# Eth_Conn.net
KiCad netlist of a schematic drawn in Altium Designer
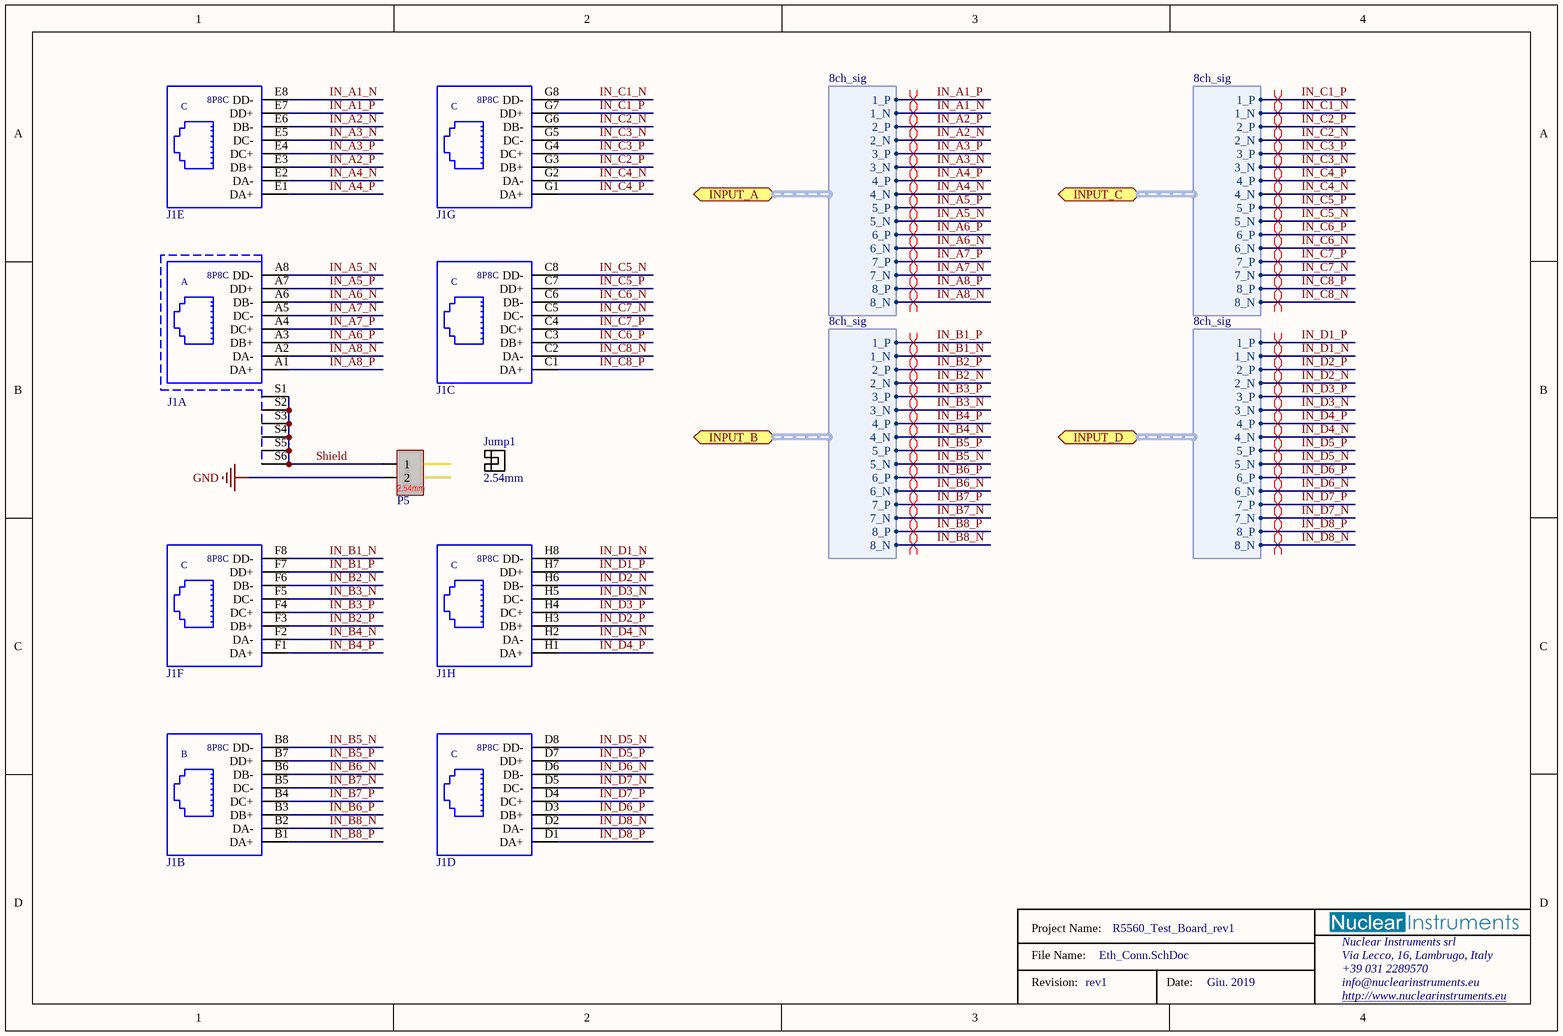
[diagram p0: Eth_Conn.SchDoc]

(export (version "E")
  (design (tool "Eeschema 10.0.6"))
  (components
    (comp (ref "J1")
      (value "Wurth_WR-MJ_RJ45_2x4_615064243321")
      (footprint "Wurth_WR-MJ_RJ45_2x4_615064243321")
      (description "RJ45 Modular Jack 2x4")
      (libsource (lib "Board_Wire_Connectors__SARAversion-84") (part "Wurth_WR-MJ_RJ45_2x4_615064243321"))
    )
    (comp (ref "Jump1") (value "2.54mm") (libsource (lib "Mechanical__SARAversion-78") (part "SNT-100-BK-G")))
    (comp (ref "P5")
      (value "Wurth_WR-PHD_2way_2.54mm_male")
      (footprint "Wurth_WR-PHD_2way_2.54mm_male")
      (description "Male 2 way 2.54 mm")
      (libsource (lib "Strip_Connectors__SARAversion-14") (part "Wurth_WR-PHD_2way_2.54mm_male"))
    )
  )
  (nets
    (net (code "2") (name "/IN_A1_N") (class "Default")
      (node (ref "J1") (pin "E8") (pinfunction "DD-_E8") (pintype "passive"))
    )
    (net (code "3") (name "/IN_A1_P") (class "Default")
      (node (ref "J1") (pin "E7") (pinfunction "DD+_E7") (pintype "passive"))
    )
    (net (code "4") (name "/IN_A2_N") (class "Default")
      (node (ref "J1") (pin "E6") (pinfunction "DB-_E6") (pintype "passive"))
    )
    (net (code "5") (name "/IN_A2_P") (class "Default")
      (node (ref "J1") (pin "E3") (pinfunction "DB+_E3") (pintype "passive"))
    )
    (net (code "6") (name "/IN_A3_N") (class "Default")
      (node (ref "J1") (pin "E5") (pinfunction "DC-_E5") (pintype "passive"))
    )
    (net (code "7") (name "/IN_A3_P") (class "Default")
      (node (ref "J1") (pin "E4") (pinfunction "DC+_E4") (pintype "passive"))
    )
    (net (code "8") (name "/IN_A4_N") (class "Default")
      (node (ref "J1") (pin "E2") (pinfunction "DA-_E2") (pintype "passive"))
    )
    (net (code "9") (name "/IN_A4_P") (class "Default")
      (node (ref "J1") (pin "E1") (pinfunction "DA+_E1") (pintype "passive"))
    )
    (net (code "10") (name "/IN_A5_N") (class "Default")
      (node (ref "J1") (pin "A8") (pinfunction "DD-_A8") (pintype "passive"))
    )
    (net (code "11") (name "/IN_A5_P") (class "Default")
      (node (ref "J1") (pin "A7") (pinfunction "DD+_A7") (pintype "passive"))
    )
    (net (code "12") (name "/IN_A6_N") (class "Default")
      (node (ref "J1") (pin "A6") (pinfunction "DB-_A6") (pintype "passive"))
    )
    (net (code "13") (name "/IN_A6_P") (class "Default")
      (node (ref "J1") (pin "A3") (pinfunction "DB+_A3") (pintype "passive"))
    )
    (net (code "14") (name "/IN_A7_N") (class "Default")
      (node (ref "J1") (pin "A5") (pinfunction "DC-_A5") (pintype "passive"))
    )
    (net (code "15") (name "/IN_A7_P") (class "Default")
      (node (ref "J1") (pin "A4") (pinfunction "DC+_A4") (pintype "passive"))
    )
    (net (code "16") (name "/IN_A8_N") (class "Default")
      (node (ref "J1") (pin "A2") (pinfunction "DA-_A2") (pintype "passive"))
    )
    (net (code "17") (name "/IN_A8_P") (class "Default")
      (node (ref "J1") (pin "A1") (pinfunction "DA+_A1") (pintype "passive"))
    )
    (net (code "18") (name "/IN_B1_N") (class "Default")
      (node (ref "J1") (pin "F8") (pinfunction "DD-_F8") (pintype "passive"))
    )
    (net (code "19") (name "/IN_B1_P") (class "Default")
      (node (ref "J1") (pin "F7") (pinfunction "DD+_F7") (pintype "passive"))
    )
    (net (code "20") (name "/IN_B2_N") (class "Default")
      (node (ref "J1") (pin "F6") (pinfunction "DB-_F6") (pintype "passive"))
    )
    (net (code "21") (name "/IN_B2_P") (class "Default")
      (node (ref "J1") (pin "F3") (pinfunction "DB+_F3") (pintype "passive"))
    )
    (net (code "22") (name "/IN_B3_N") (class "Default")
      (node (ref "J1") (pin "F5") (pinfunction "DC-_F5") (pintype "passive"))
    )
    (net (code "23") (name "/IN_B3_P") (class "Default")
      (node (ref "J1") (pin "F4") (pinfunction "DC+_F4") (pintype "passive"))
    )
    (net (code "24") (name "/IN_B4_N") (class "Default")
      (node (ref "J1") (pin "F2") (pinfunction "DA-_F2") (pintype "passive"))
    )
    (net (code "25") (name "/IN_B4_P") (class "Default")
      (node (ref "J1") (pin "F1") (pinfunction "DA+_F1") (pintype "passive"))
    )
    (net (code "26") (name "/IN_B5_N") (class "Default")
      (node (ref "J1") (pin "B8") (pinfunction "DD-_B8") (pintype "passive"))
    )
    (net (code "27") (name "/IN_B5_P") (class "Default")
      (node (ref "J1") (pin "B7") (pinfunction "DD+_B7") (pintype "passive"))
    )
    (net (code "28") (name "/IN_B6_N") (class "Default")
      (node (ref "J1") (pin "B6") (pinfunction "DB-_B6") (pintype "passive"))
    )
    (net (code "29") (name "/IN_B6_P") (class "Default")
      (node (ref "J1") (pin "B3") (pinfunction "DB+_B3") (pintype "passive"))
    )
    (net (code "30") (name "/IN_B7_N") (class "Default")
      (node (ref "J1") (pin "B5") (pinfunction "DC-_B5") (pintype "passive"))
    )
    (net (code "31") (name "/IN_B7_P") (class "Default")
      (node (ref "J1") (pin "B4") (pinfunction "DC+_B4") (pintype "passive"))
    )
    (net (code "32") (name "/IN_B8_N") (class "Default")
      (node (ref "J1") (pin "B2") (pinfunction "DA-_B2") (pintype "passive"))
    )
    (net (code "33") (name "/IN_B8_P") (class "Default")
      (node (ref "J1") (pin "B1") (pinfunction "DA+_B1") (pintype "passive"))
    )
    (net (code "34") (name "/IN_C1_N") (class "Default")
      (node (ref "J1") (pin "G8") (pinfunction "DD-_G8") (pintype "passive"))
    )
    (net (code "35") (name "/IN_C1_P") (class "Default")
      (node (ref "J1") (pin "G7") (pinfunction "DD+_G7") (pintype "passive"))
    )
    (net (code "36") (name "/IN_C2_N") (class "Default")
      (node (ref "J1") (pin "G6") (pinfunction "DB-_G6") (pintype "passive"))
    )
    (net (code "37") (name "/IN_C2_P") (class "Default")
      (node (ref "J1") (pin "G3") (pinfunction "DB+_G3") (pintype "passive"))
    )
    (net (code "38") (name "/IN_C3_N") (class "Default")
      (node (ref "J1") (pin "G5") (pinfunction "DC-_G5") (pintype "passive"))
    )
    (net (code "39") (name "/IN_C3_P") (class "Default")
      (node (ref "J1") (pin "G4") (pinfunction "DC+_G4") (pintype "passive"))
    )
    (net (code "40") (name "/IN_C4_N") (class "Default")
      (node (ref "J1") (pin "G2") (pinfunction "DA-_G2") (pintype "passive"))
    )
    (net (code "41") (name "/IN_C4_P") (class "Default")
      (node (ref "J1") (pin "G1") (pinfunction "DA+_G1") (pintype "passive"))
    )
    (net (code "42") (name "/IN_C5_N") (class "Default")
      (node (ref "J1") (pin "C8") (pinfunction "DD-_C8") (pintype "passive"))
    )
    (net (code "43") (name "/IN_C5_P") (class "Default")
      (node (ref "J1") (pin "C7") (pinfunction "DD+_C7") (pintype "passive"))
    )
    (net (code "44") (name "/IN_C6_N") (class "Default")
      (node (ref "J1") (pin "C6") (pinfunction "DB-_C6") (pintype "passive"))
    )
    (net (code "45") (name "/IN_C6_P") (class "Default")
      (node (ref "J1") (pin "C3") (pinfunction "DB+_C3") (pintype "passive"))
    )
    (net (code "46") (name "/IN_C7_N") (class "Default")
      (node (ref "J1") (pin "C5") (pinfunction "DC-_C5") (pintype "passive"))
    )
    (net (code "47") (name "/IN_C7_P") (class "Default")
      (node (ref "J1") (pin "C4") (pinfunction "DC+_C4") (pintype "passive"))
    )
    (net (code "48") (name "/IN_C8_N") (class "Default")
      (node (ref "J1") (pin "C2") (pinfunction "DA-_C2") (pintype "passive"))
    )
    (net (code "49") (name "/IN_C8_P") (class "Default")
      (node (ref "J1") (pin "C1") (pinfunction "DA+_C1") (pintype "passive"))
    )
    (net (code "50") (name "/IN_D1_N") (class "Default")
      (node (ref "J1") (pin "H8") (pinfunction "DD-_H8") (pintype "passive"))
    )
    (net (code "51") (name "/IN_D1_P") (class "Default")
      (node (ref "J1") (pin "H7") (pinfunction "DD+_H7") (pintype "passive"))
    )
    (net (code "52") (name "/IN_D2_N") (class "Default")
      (node (ref "J1") (pin "H6") (pinfunction "DB-_H6") (pintype "passive"))
    )
    (net (code "53") (name "/IN_D2_P") (class "Default")
      (node (ref "J1") (pin "H3") (pinfunction "DB+_H3") (pintype "passive"))
    )
    (net (code "54") (name "/IN_D3_N") (class "Default")
      (node (ref "J1") (pin "H5") (pinfunction "DC-_H5") (pintype "passive"))
    )
    (net (code "55") (name "/IN_D3_P") (class "Default")
      (node (ref "J1") (pin "H4") (pinfunction "DC+_H4") (pintype "passive"))
    )
    (net (code "56") (name "/IN_D4_N") (class "Default")
      (node (ref "J1") (pin "H2") (pinfunction "DA-_H2") (pintype "passive"))
    )
    (net (code "57") (name "/IN_D4_P") (class "Default")
      (node (ref "J1") (pin "H1") (pinfunction "DA+_H1") (pintype "passive"))
    )
    (net (code "58") (name "/IN_D5_N") (class "Default")
      (node (ref "J1") (pin "D8") (pinfunction "DD-_D8") (pintype "passive"))
    )
    (net (code "59") (name "/IN_D5_P") (class "Default")
      (node (ref "J1") (pin "D7") (pinfunction "DD+_D7") (pintype "passive"))
    )
    (net (code "60") (name "/IN_D6_N") (class "Default")
      (node (ref "J1") (pin "D6") (pinfunction "DB-_D6") (pintype "passive"))
    )
    (net (code "61") (name "/IN_D6_P") (class "Default")
      (node (ref "J1") (pin "D3") (pinfunction "DB+_D3") (pintype "passive"))
    )
    (net (code "62") (name "/IN_D7_N") (class "Default")
      (node (ref "J1") (pin "D5") (pinfunction "DC-_D5") (pintype "passive"))
    )
    (net (code "63") (name "/IN_D7_P") (class "Default")
      (node (ref "J1") (pin "D4") (pinfunction "DC+_D4") (pintype "passive"))
    )
    (net (code "64") (name "/IN_D8_N") (class "Default")
      (node (ref "J1") (pin "D2") (pinfunction "DA-_D2") (pintype "passive"))
    )
    (net (code "65") (name "/IN_D8_P") (class "Default")
      (node (ref "J1") (pin "D1") (pinfunction "DA+_D1") (pintype "passive"))
    )
    (net (code "66") (name "/Shield") (class "Default")
      (node (ref "J1") (pin "S1") (pinfunction "S1_S1") (pintype "passive"))
      (node (ref "J1") (pin "S2") (pinfunction "S2_S2") (pintype "passive"))
      (node (ref "J1") (pin "S3") (pinfunction "S3_S3") (pintype "passive"))
      (node (ref "J1") (pin "S4") (pinfunction "S4_S4") (pintype "passive"))
      (node (ref "J1") (pin "S5") (pinfunction "S5_S5") (pintype "passive"))
      (node (ref "J1") (pin "S6") (pinfunction "S6_S6") (pintype "passive"))
      (node (ref "P5") (pin "1") (pinfunction "1_1") (pintype "passive"))
    )
    (net (code "68") (name "GND") (class "Default")
      (node (ref "P5") (pin "2") (pinfunction "2_2") (pintype "passive"))
    )
  )
)
